# CH340T9T-R0.net
KiCad netlist of a schematic drawn in Altium Designer
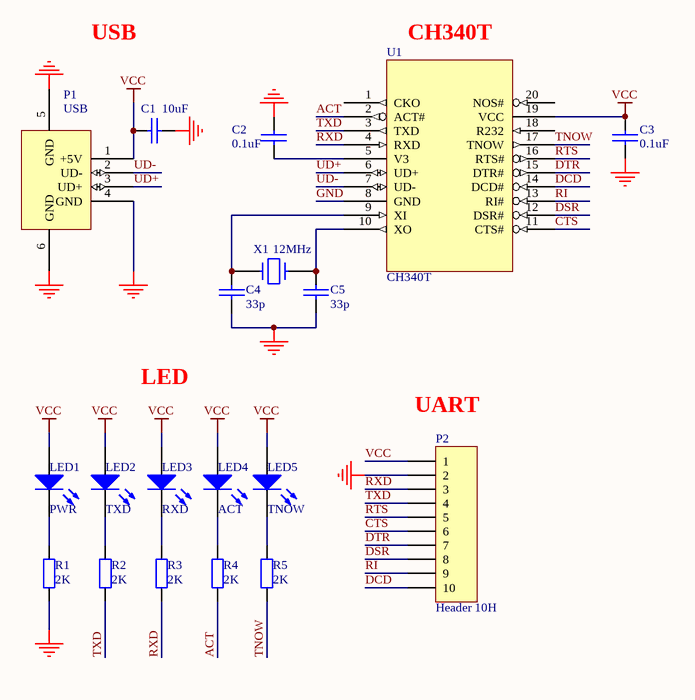
[diagram p0: CH340T9T-R0.SchDoc]

(export (version "E")
  (design (tool "Eeschema 10.0.6"))
  (components
    (comp (ref "C1")
      (value "10uF")
      (footprint "3216_C")
      (description "Capacitor")
      (libsource (lib "*") (part "CAP"))
    )
    (comp (ref "C2")
      (value "0.1uF")
      (footprint "0603_C")
      (description "Capacitor")
      (libsource (lib "*") (part "CAP"))
    )
    (comp (ref "C3")
      (value "0.1uF")
      (footprint "0603_C")
      (description "Capacitor")
      (libsource (lib "*") (part "CAP"))
    )
    (comp (ref "C4")
      (value "33p")
      (footprint "0603_C")
      (description "Capacitor")
      (libsource (lib "") (part "CAP_1"))
    )
    (comp (ref "C5")
      (value "33p")
      (footprint "0603_C")
      (description "Capacitor")
      (libsource (lib "") (part "CAP_1"))
    )
    (comp (ref "LED1")
      (value "PWR")
      (footprint "0603+")
      (description "Typical RED, GREEN, YELLOW, AMBER GaAs LED")
      (libsource (lib "*") (part "LED2"))
    )
    (comp (ref "LED2")
      (value "TXD")
      (footprint "0603+")
      (description "Typical RED, GREEN, YELLOW, AMBER GaAs LED")
      (libsource (lib "*") (part "LED2"))
    )
    (comp (ref "LED3")
      (value "RXD")
      (footprint "0603+")
      (description "Typical RED, GREEN, YELLOW, AMBER GaAs LED")
      (libsource (lib "*") (part "LED2"))
    )
    (comp (ref "LED4")
      (value "ACT")
      (footprint "0603+")
      (description "Typical RED, GREEN, YELLOW, AMBER GaAs LED")
      (libsource (lib "*") (part "LED2"))
    )
    (comp (ref "LED5")
      (value "TNOW")
      (footprint "0603+")
      (description "Typical RED, GREEN, YELLOW, AMBER GaAs LED")
      (libsource (lib "*") (part "LED2"))
    )
    (comp (ref "P1") (value "USB") (footprint "USBAM") (libsource (lib "*") (part "USB")))
    (comp (ref "P2")
      (value "Header 10H")
      (footprint "SIP10-2.54mm")
      (description "Header, 10-Pin, Right Angle")
      (fields (field (name "PUBLISHER") "Altium Limited"))
      (libsource (lib "Miscellaneous Connectors") (part "Header 10H"))
    )
    (comp (ref "R1")
      (value "2K")
      (footprint "0603")
      (description "Resistor")
      (libsource (lib "*") (part "Res2"))
    )
    (comp (ref "R2")
      (value "2K")
      (footprint "0603")
      (description "Resistor")
      (libsource (lib "*") (part "Res2"))
    )
    (comp (ref "R3")
      (value "2K")
      (footprint "0603")
      (description "Resistor")
      (libsource (lib "*") (part "Res2"))
    )
    (comp (ref "R4")
      (value "2K")
      (footprint "0603")
      (description "Resistor")
      (libsource (lib "*") (part "Res2"))
    )
    (comp (ref "R5")
      (value "2K")
      (footprint "0603")
      (description "Resistor")
      (libsource (lib "*") (part "Res2"))
    )
    (comp (ref "U1")
      (value "CH340T")
      (footprint "SSOP20")
      (description "USB to TTL Serial / UART,  USB to IrDA")
      (libsource (lib "CHXXX") (part "CH340T"))
    )
    (comp (ref "X1")
      (value "12MHz")
      (footprint "XT3225")
      (description "Crystal")
      (libsource (lib "*") (part "CRYSTAL"))
    )
  )
  (nets
    (net (code "1") (name "/ACT") (class "Default")
      (node (ref "R4") (pin "2") (pinfunction "2_2") (pintype "passive"))
      (node (ref "U1") (pin "2") (pinfunction "ACT#_2") (pintype "output"))
    )
    (net (code "2") (name "/CTS") (class "Default")
      (node (ref "P2") (pin "6") (pinfunction "6_6") (pintype "passive"))
      (node (ref "U1") (pin "11") (pinfunction "CTS#_11") (pintype "input"))
    )
    (net (code "3") (name "/DCD") (class "Default")
      (node (ref "P2") (pin "10") (pinfunction "10_10") (pintype "passive"))
      (node (ref "U1") (pin "14") (pinfunction "DCD#_14") (pintype "input"))
    )
    (net (code "4") (name "/DSR") (class "Default")
      (node (ref "P2") (pin "8") (pinfunction "8_8") (pintype "passive"))
      (node (ref "U1") (pin "12") (pinfunction "DSR#_12") (pintype "input"))
    )
    (net (code "5") (name "/DTR") (class "Default")
      (node (ref "P2") (pin "7") (pinfunction "7_7") (pintype "passive"))
      (node (ref "U1") (pin "15") (pinfunction "DTR#_15") (pintype "output"))
    )
    (net (code "6") (name "/RI") (class "Default")
      (node (ref "P2") (pin "9") (pinfunction "9_9") (pintype "passive"))
      (node (ref "U1") (pin "13") (pinfunction "RI#_13") (pintype "input"))
    )
    (net (code "7") (name "/RTS") (class "Default")
      (node (ref "P2") (pin "5") (pinfunction "5_5") (pintype "passive"))
      (node (ref "U1") (pin "16") (pinfunction "RTS#_16") (pintype "output"))
    )
    (net (code "8") (name "/RXD") (class "Default")
      (node (ref "P2") (pin "3") (pinfunction "3_3") (pintype "passive"))
      (node (ref "R3") (pin "2") (pinfunction "2_2") (pintype "passive"))
      (node (ref "U1") (pin "4") (pinfunction "RXD_4") (pintype "input"))
    )
    (net (code "9") (name "/TNOW") (class "Default")
      (node (ref "R5") (pin "2") (pinfunction "2_2") (pintype "passive"))
      (node (ref "U1") (pin "17") (pinfunction "TNOW_17") (pintype "output"))
    )
    (net (code "10") (name "/TXD") (class "Default")
      (node (ref "P2") (pin "4") (pinfunction "4_4") (pintype "passive"))
      (node (ref "R2") (pin "2") (pinfunction "2_2") (pintype "passive"))
      (node (ref "U1") (pin "3") (pinfunction "TXD_3") (pintype "output"))
    )
    (net (code "11") (name "/UD+") (class "Default")
      (node (ref "P1") (pin "3") (pinfunction "UD+_3") (pintype "bidirectional"))
      (node (ref "U1") (pin "6") (pinfunction "UD+_6") (pintype "bidirectional"))
    )
    (net (code "12") (name "/UD-") (class "Default")
      (node (ref "P1") (pin "2") (pinfunction "UD-_2") (pintype "bidirectional"))
      (node (ref "U1") (pin "7") (pinfunction "UD-_7") (pintype "bidirectional"))
    )
    (net (code "13") (name "GND") (class "Default")
      (node (ref "C1") (pin "2") (pinfunction "2_2") (pintype "passive"))
      (node (ref "C2") (pin "2") (pinfunction "2_2") (pintype "passive"))
      (node (ref "C3") (pin "2") (pinfunction "2_2") (pintype "passive"))
      (node (ref "C4") (pin "2") (pinfunction "2_2") (pintype "passive"))
      (node (ref "C5") (pin "2") (pinfunction "2_2") (pintype "passive"))
      (node (ref "P1") (pin "4") (pinfunction "GND_4") (pintype "power_in"))
      (node (ref "P1") (pin "5") (pinfunction "GND_5") (pintype "power_in"))
      (node (ref "P1") (pin "6") (pinfunction "GND_6") (pintype "power_in"))
      (node (ref "P2") (pin "2") (pinfunction "2_2") (pintype "passive"))
      (node (ref "R1") (pin "2") (pinfunction "2_2") (pintype "passive"))
      (node (ref "U1") (pin "8") (pinfunction "GND_8") (pintype "power_in"))
    )
    (net (code "14") (name "Net-(LED1-K)") (class "Default")
      (node (ref "LED1") (pin "2") (pinfunction "K_2") (pintype "passive"))
      (node (ref "R1") (pin "1") (pinfunction "1_1") (pintype "passive"))
    )
    (net (code "15") (name "Net-(LED2-K)") (class "Default")
      (node (ref "LED2") (pin "2") (pinfunction "K_2") (pintype "passive"))
      (node (ref "R2") (pin "1") (pinfunction "1_1") (pintype "passive"))
    )
    (net (code "16") (name "Net-(LED3-K)") (class "Default")
      (node (ref "LED3") (pin "2") (pinfunction "K_2") (pintype "passive"))
      (node (ref "R3") (pin "1") (pinfunction "1_1") (pintype "passive"))
    )
    (net (code "17") (name "Net-(LED4-K)") (class "Default")
      (node (ref "LED4") (pin "2") (pinfunction "K_2") (pintype "passive"))
      (node (ref "R4") (pin "1") (pinfunction "1_1") (pintype "passive"))
    )
    (net (code "18") (name "Net-(LED5-K)") (class "Default")
      (node (ref "LED5") (pin "2") (pinfunction "K_2") (pintype "passive"))
      (node (ref "R5") (pin "1") (pinfunction "1_1") (pintype "passive"))
    )
    (net (code "19") (name "Net-(U1-V3)") (class "Default")
      (node (ref "C2") (pin "1") (pinfunction "1_1") (pintype "passive"))
      (node (ref "U1") (pin "5") (pinfunction "V3_5") (pintype "power_in"))
    )
    (net (code "20") (name "Net-(U1-XI)") (class "Default")
      (node (ref "C4") (pin "1") (pinfunction "1_1") (pintype "passive"))
      (node (ref "U1") (pin "9") (pinfunction "XI_9") (pintype "input"))
      (node (ref "X1") (pin "1") (pinfunction "1_1") (pintype "passive"))
    )
    (net (code "21") (name "Net-(U1-XO)") (class "Default")
      (node (ref "C5") (pin "1") (pinfunction "1_1") (pintype "passive"))
      (node (ref "U1") (pin "10") (pinfunction "XO_10") (pintype "output"))
      (node (ref "X1") (pin "3") (pinfunction "3_3") (pintype "passive"))
    )
    (net (code "22") (name "VCC") (class "Default")
      (node (ref "C1") (pin "1") (pinfunction "1_1") (pintype "passive"))
      (node (ref "C3") (pin "1") (pinfunction "1_1") (pintype "passive"))
      (node (ref "LED1") (pin "1") (pinfunction "A_1") (pintype "passive"))
      (node (ref "LED2") (pin "1") (pinfunction "A_1") (pintype "passive"))
      (node (ref "LED3") (pin "1") (pinfunction "A_1") (pintype "passive"))
      (node (ref "LED4") (pin "1") (pinfunction "A_1") (pintype "passive"))
      (node (ref "LED5") (pin "1") (pinfunction "A_1") (pintype "passive"))
      (node (ref "P1") (pin "1") (pinfunction "+5V_1") (pintype "power_in"))
      (node (ref "P2") (pin "1") (pinfunction "1_1") (pintype "passive"))
      (node (ref "U1") (pin "19") (pinfunction "VCC_19") (pintype "power_in"))
    )
    (net (code "23") (name "unconnected-(U1-CKO-Pad1)") (class "Default")
      (node (ref "U1") (pin "1") (pinfunction "CKO_1") (pintype "output"))
    )
    (net (code "24") (name "unconnected-(U1-NOS#-Pad20)") (class "Default")
      (node (ref "U1") (pin "20") (pinfunction "NOS#_20") (pintype "input"))
    )
    (net (code "25") (name "unconnected-(U1-R232-Pad18)") (class "Default")
      (node (ref "U1") (pin "18") (pinfunction "R232_18") (pintype "input"))
    )
  )
)
